# MIXR_Processing_-_ESP32_Peripherals.net
KiCad netlist of a schematic drawn in Altium Designer
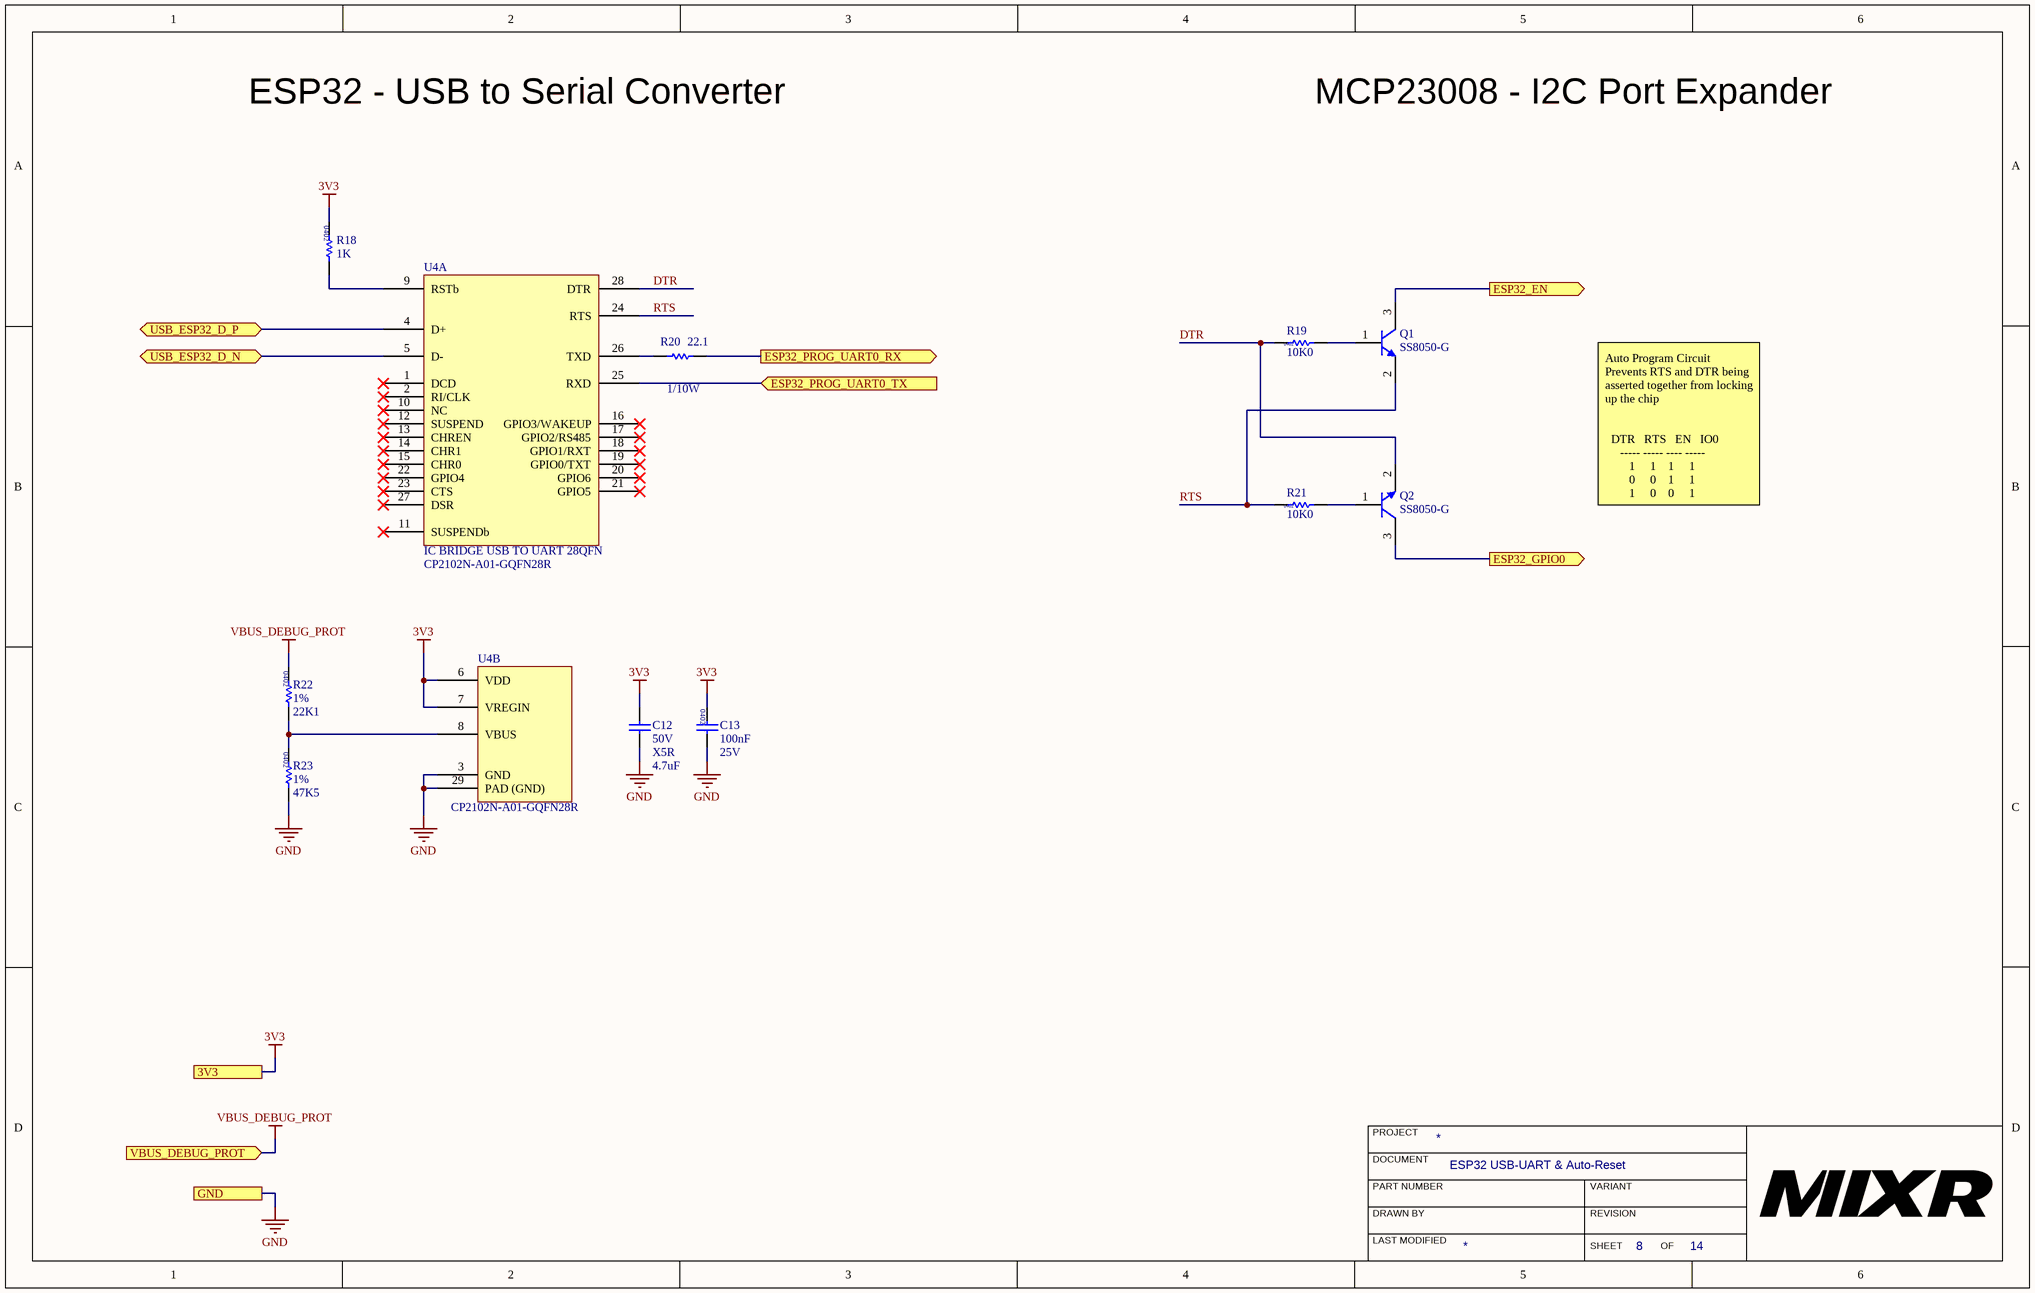
[diagram p0: MIXR Processing - ESP32 Peripherals.SchDoc]

(export (version "E")
  (design (tool "Eeschema 10.0.6"))
  (components
    (comp (ref "C12")
      (value "4.7uF")
      (footprint "CAP, 0805")
      (description "4.7µF ±20% 50V Ceramic Capacitor X5R 0805 (2012 Metric)")
      (fields
        (field (name "TOLERANCE") "±20%")
        (field (name "VOLTAGE - RATED") "50V")
        (field (name "TEMPERATURE COEFFICIENT") "X5R")
        (field (name "Comment") "CAP CER 4.7UF 50V 10% X5R 0805")
      )
      (libsource (lib "Schematic Diagrams") (part "CAP CER 4.7UF 50V 10% X5R 0805"))
    )
    (comp (ref "C13")
      (value "CAP CER 0.1UF 16V X7R 0402")
      (footprint "CAP 0402")
      (description "Cap Ceramic 0.1uF 25V X7R 10% SMD 0402 125C Paper T/R")
      (fields
        (field (name "TOLERANCE") "10%")
        (field (name "CAPACITANCE") "100nF")
        (field (name "VOLTAGE") "25V")
        (field (name "MANUFACTURER") "Murata")
      )
      (libsource (lib "Schematic Diagrams") (part "CAP CER 0.1UF 16V X7R 0402"))
    )
    (comp (ref "Q1")
      (value "SS8050-G")
      (footprint "MOSFET N-CH 30V 6.2A 0.9W SOT-23")
      (description "NPN TRANSISTOR 1.5A 40V SOT-23 R")
      (fields (field (name "MANUFACTURER") "Comchip") (field (name "MANUFACTURER PART NUMBER") "SS8050-G"))
      (libsource (lib "Schematic Diagrams") (part "BJT NPN 40V 1.5A SOT-23"))
    )
    (comp (ref "Q2")
      (value "SS8050-G")
      (footprint "MOSFET N-CH 30V 6.2A 0.9W SOT-23")
      (description "NPN TRANSISTOR 1.5A 40V SOT-23 R")
      (fields (field (name "MANUFACTURER") "Comchip") (field (name "MANUFACTURER PART NUMBER") "SS8050-G"))
      (libsource (lib "Schematic Diagrams") (part "BJT NPN 40V 1.5A SOT-23"))
    )
    (comp (ref "R18")
      (value "RES 1K OHM 0.1% 1/16W 0402")
      (footprint "RES 0402")
      (description "RES SMD 1K OHM 0.1% 1/16W 0402")
      (fields
        (field (name "MANUFACTURER") "Yageo")
        (field (name "MANUFACTURER PART NUMBER") "RT0402BRE071KL")
        (field (name "RESISTANCE") "1K")
      )
      (libsource (lib "Schematic Diagrams") (part "RES 1K OHM 0.1% 1/16W 0402"))
    )
    (comp (ref "R19")
      (value "RES 10K OHM 1% 1/16W 0402")
      (footprint "RES 0402")
      (description "Surface Mount Thick Film Resistor, Rc Series, 10 Kohm, 62.5 Mw, - 1%, 50 V, 0402 [1005 Metric]")
      (fields
        (field (name "TOLERANCE") "1%")
        (field (name "RESISTANCE") "10K0")
        (field (name "MANUFACTURER") "Yageo")
      )
      (libsource (lib "Schematic Diagrams") (part "RES 10K OHM 1% 1/16W 0402"))
    )
    (comp (ref "R20")
      (value "RES 22.1 OHM 1% 1/10W 0603")
      (footprint "RES, 0603")
      (description "22.1 Ohm ±1% 0.1W, 1/10W Chip Resistor 0603 (1608 Metric) Moisture Resistant Thick Film")
      (fields
        (field (name "TOLERANCE") "±1%")
        (field (name "RESISTANCE") "22.1")
        (field (name "POWER") "1/10W")
      )
      (libsource (lib "Schematic Diagrams") (part "RES 22.1 OHM 1% 1/10W 0603"))
    )
    (comp (ref "R21")
      (value "RES 10K OHM 1% 1/16W 0402")
      (footprint "RES 0402")
      (description "Surface Mount Thick Film Resistor, Rc Series, 10 Kohm, 62.5 Mw, - 1%, 50 V, 0402 [1005 Metric]")
      (fields
        (field (name "TOLERANCE") "1%")
        (field (name "RESISTANCE") "10K0")
        (field (name "MANUFACTURER") "Yageo")
      )
      (libsource (lib "Schematic Diagrams") (part "RES 10K OHM 1% 1/16W 0402"))
    )
    (comp (ref "R22")
      (value "RES 22.1K OHM 1% 1/16W 0402")
      (footprint "RES 0402")
      (description "RES SMD 22.1K OHM 1% 1/16W 0402")
      (fields
        (field (name "MANUFACTURER") "Stackpole Electronics")
        (field (name "MANUFACTURER PART NUMBER") "RMCF0402FT22K1")
        (field (name "TOLERANCE") "1%")
        (field (name "RESISTANCE") "22K1")
      )
      (libsource (lib "Schematic Diagrams") (part "RES 22.1K OHM 1% 1/16W 0402"))
    )
    (comp (ref "R23")
      (value "RES 47.5K OHM 1% 1/16W 0402")
      (footprint "RES 0402")
      (description "RES SMD 47.5K OHM 1% 1/16W 0402")
      (fields
        (field (name "MANUFACTURER") "Yageo")
        (field (name "MANUFACTURER PART NUMBER") "RC0402FR-0747K5L")
        (field (name "TOLERANCE") "1%")
        (field (name "RESISTANCE") "47K5")
      )
      (libsource (lib "Schematic Diagrams") (part "RES 47.5K OHM 1% 1/16W 0402"))
    )
    (comp (ref "U4")
      (value "IC BRIDGE USB TO UART 28QFN")
      (footprint "QFN50P500X500X80_HS-29M")
      (fields
        (field (name "MANUFACTURER") "Silicon Labs")
        (field (name "MANUFACTURER PART NUMBER") "CP2102N-A01-GQFN28R")
      )
      (libsource (lib "Schematic Diagrams") (part "IC BRIDGE USB TO UART 28QFN"))
    )
  )
  (nets
    (net (code "1") (name "/DTR") (class "Default")
      (node (ref "Q2") (pin "2") (pinfunction "E_2") (pintype "passive"))
      (node (ref "R19") (pin "1") (pinfunction "1_1") (pintype "passive"))
      (node (ref "U4") (pin "28") (pinfunction "DTR_28") (pintype "passive"))
    )
    (net (code "2") (name "/ESP32_EN") (class "Default")
      (node (ref "Q1") (pin "3") (pinfunction "E_3") (pintype "passive"))
    )
    (net (code "3") (name "/ESP32_GPIO0") (class "Default")
      (node (ref "Q2") (pin "3") (pinfunction "E_3") (pintype "passive"))
    )
    (net (code "4") (name "/ESP32_PROG_UART0_RX") (class "Default")
      (node (ref "R20") (pin "2") (pinfunction "2_2") (pintype "passive"))
    )
    (net (code "5") (name "/ESP32_PROG_UART0_TX") (class "Default")
      (node (ref "U4") (pin "25") (pinfunction "RXD_25") (pintype "passive"))
    )
    (net (code "6") (name "/RTS") (class "Default")
      (node (ref "Q1") (pin "2") (pinfunction "E_2") (pintype "passive"))
      (node (ref "R21") (pin "1") (pinfunction "1_1") (pintype "passive"))
      (node (ref "U4") (pin "24") (pinfunction "RTS_24") (pintype "passive"))
    )
    (net (code "7") (name "/USB_ESP32_D_N") (class "Default")
      (node (ref "U4") (pin "5") (pinfunction "D-_5") (pintype "passive"))
    )
    (net (code "8") (name "/USB_ESP32_D_P") (class "Default")
      (node (ref "U4") (pin "4") (pinfunction "D+_4") (pintype "passive"))
    )
    (net (code "9") (name "3V3") (class "Default")
      (node (ref "C12") (pin "1") (pinfunction "1_1") (pintype "passive"))
      (node (ref "C13") (pin "1") (pinfunction "1_1") (pintype "passive"))
      (node (ref "R18") (pin "1") (pinfunction "1_1") (pintype "passive"))
      (node (ref "U4") (pin "6") (pinfunction "VDD_6") (pintype "passive"))
      (node (ref "U4") (pin "7") (pinfunction "VREGIN_7") (pintype "passive"))
    )
    (net (code "10") (name "GND") (class "Default")
      (node (ref "C12") (pin "2") (pinfunction "2_2") (pintype "passive"))
      (node (ref "C13") (pin "2") (pinfunction "2_2") (pintype "passive"))
      (node (ref "R23") (pin "2") (pinfunction "2_2") (pintype "passive"))
      (node (ref "U4") (pin "29") (pinfunction "PAD_(GND)_29") (pintype "passive"))
      (node (ref "U4") (pin "3") (pinfunction "GND_3") (pintype "passive"))
    )
    (net (code "11") (name "Net-(Q1-B)") (class "Default")
      (node (ref "Q1") (pin "1") (pinfunction "B_1") (pintype "passive"))
      (node (ref "R19") (pin "2") (pinfunction "2_2") (pintype "passive"))
    )
    (net (code "12") (name "Net-(Q2-B)") (class "Default")
      (node (ref "Q2") (pin "1") (pinfunction "B_1") (pintype "passive"))
      (node (ref "R21") (pin "2") (pinfunction "2_2") (pintype "passive"))
    )
    (net (code "13") (name "Net-(U4A-RSTb)") (class "Default")
      (node (ref "R18") (pin "2") (pinfunction "2_2") (pintype "passive"))
      (node (ref "U4") (pin "9") (pinfunction "RSTb_9") (pintype "passive"))
    )
    (net (code "14") (name "Net-(U4A-TXD)") (class "Default")
      (node (ref "R20") (pin "1") (pinfunction "1_1") (pintype "passive"))
      (node (ref "U4") (pin "26") (pinfunction "TXD_26") (pintype "passive"))
    )
    (net (code "15") (name "Net-(U4B-VBUS)") (class "Default")
      (node (ref "R22") (pin "2") (pinfunction "2_2") (pintype "passive"))
      (node (ref "R23") (pin "1") (pinfunction "1_1") (pintype "passive"))
      (node (ref "U4") (pin "8") (pinfunction "VBUS_8") (pintype "passive"))
    )
    (net (code "16") (name "VBUS_DEBUG_PROT") (class "Default")
      (node (ref "R22") (pin "1") (pinfunction "1_1") (pintype "passive"))
    )
    (net (code "17") (name "unconnected-(U4A-CHR0-Pad15)") (class "Default")
      (node (ref "U4") (pin "15") (pinfunction "CHR0_15") (pintype "passive+no_connect"))
    )
    (net (code "18") (name "unconnected-(U4A-CHR1-Pad14)") (class "Default")
      (node (ref "U4") (pin "14") (pinfunction "CHR1_14") (pintype "passive+no_connect"))
    )
    (net (code "19") (name "unconnected-(U4A-CHREN-Pad13)") (class "Default")
      (node (ref "U4") (pin "13") (pinfunction "CHREN_13") (pintype "passive+no_connect"))
    )
    (net (code "20") (name "unconnected-(U4A-CTS-Pad23)") (class "Default")
      (node (ref "U4") (pin "23") (pinfunction "CTS_23") (pintype "passive+no_connect"))
    )
    (net (code "21") (name "unconnected-(U4A-DCD-Pad1)") (class "Default")
      (node (ref "U4") (pin "1") (pinfunction "DCD_1") (pintype "passive+no_connect"))
    )
    (net (code "22") (name "unconnected-(U4A-DSR-Pad27)") (class "Default")
      (node (ref "U4") (pin "27") (pinfunction "DSR_27") (pintype "passive+no_connect"))
    )
    (net (code "23") (name "unconnected-(U4A-GPIO0{slash}TXT-Pad19)") (class "Default")
      (node (ref "U4") (pin "19") (pinfunction "GPIO0/TXT_19") (pintype "passive+no_connect"))
    )
    (net (code "24") (name "unconnected-(U4A-GPIO1{slash}RXT-Pad18)") (class "Default")
      (node (ref "U4") (pin "18") (pinfunction "GPIO1/RXT_18") (pintype "passive+no_connect"))
    )
    (net (code "25") (name "unconnected-(U4A-GPIO2{slash}RS485-Pad17)") (class "Default")
      (node (ref "U4") (pin "17") (pinfunction "GPIO2/RS485_17") (pintype "passive+no_connect"))
    )
    (net (code "26") (name "unconnected-(U4A-GPIO3{slash}WAKEUP-Pad16)") (class "Default")
      (node (ref "U4") (pin "16") (pinfunction "GPIO3/WAKEUP_16") (pintype "passive+no_connect"))
    )
    (net (code "27") (name "unconnected-(U4A-GPIO4-Pad22)") (class "Default")
      (node (ref "U4") (pin "22") (pinfunction "GPIO4_22") (pintype "passive+no_connect"))
    )
    (net (code "28") (name "unconnected-(U4A-GPIO5-Pad21)") (class "Default")
      (node (ref "U4") (pin "21") (pinfunction "GPIO5_21") (pintype "passive+no_connect"))
    )
    (net (code "29") (name "unconnected-(U4A-GPIO6-Pad20)") (class "Default")
      (node (ref "U4") (pin "20") (pinfunction "GPIO6_20") (pintype "passive+no_connect"))
    )
    (net (code "30") (name "unconnected-(U4A-NC-Pad10)") (class "Default")
      (node (ref "U4") (pin "10") (pinfunction "NC_10") (pintype "passive+no_connect"))
    )
    (net (code "31") (name "unconnected-(U4A-RI{slash}CLK-Pad2)") (class "Default")
      (node (ref "U4") (pin "2") (pinfunction "RI/CLK_2") (pintype "passive+no_connect"))
    )
    (net (code "32") (name "unconnected-(U4A-SUSPEND-Pad12)") (class "Default")
      (node (ref "U4") (pin "12") (pinfunction "SUSPEND_12") (pintype "passive+no_connect"))
    )
    (net (code "33") (name "unconnected-(U4A-SUSPENDb-Pad11)") (class "Default")
      (node (ref "U4") (pin "11") (pinfunction "SUSPENDb_11") (pintype "passive+no_connect"))
    )
  )
)
